# Rx_Universal_Schematic.net
KiCad netlist of a schematic drawn in Altium Designer
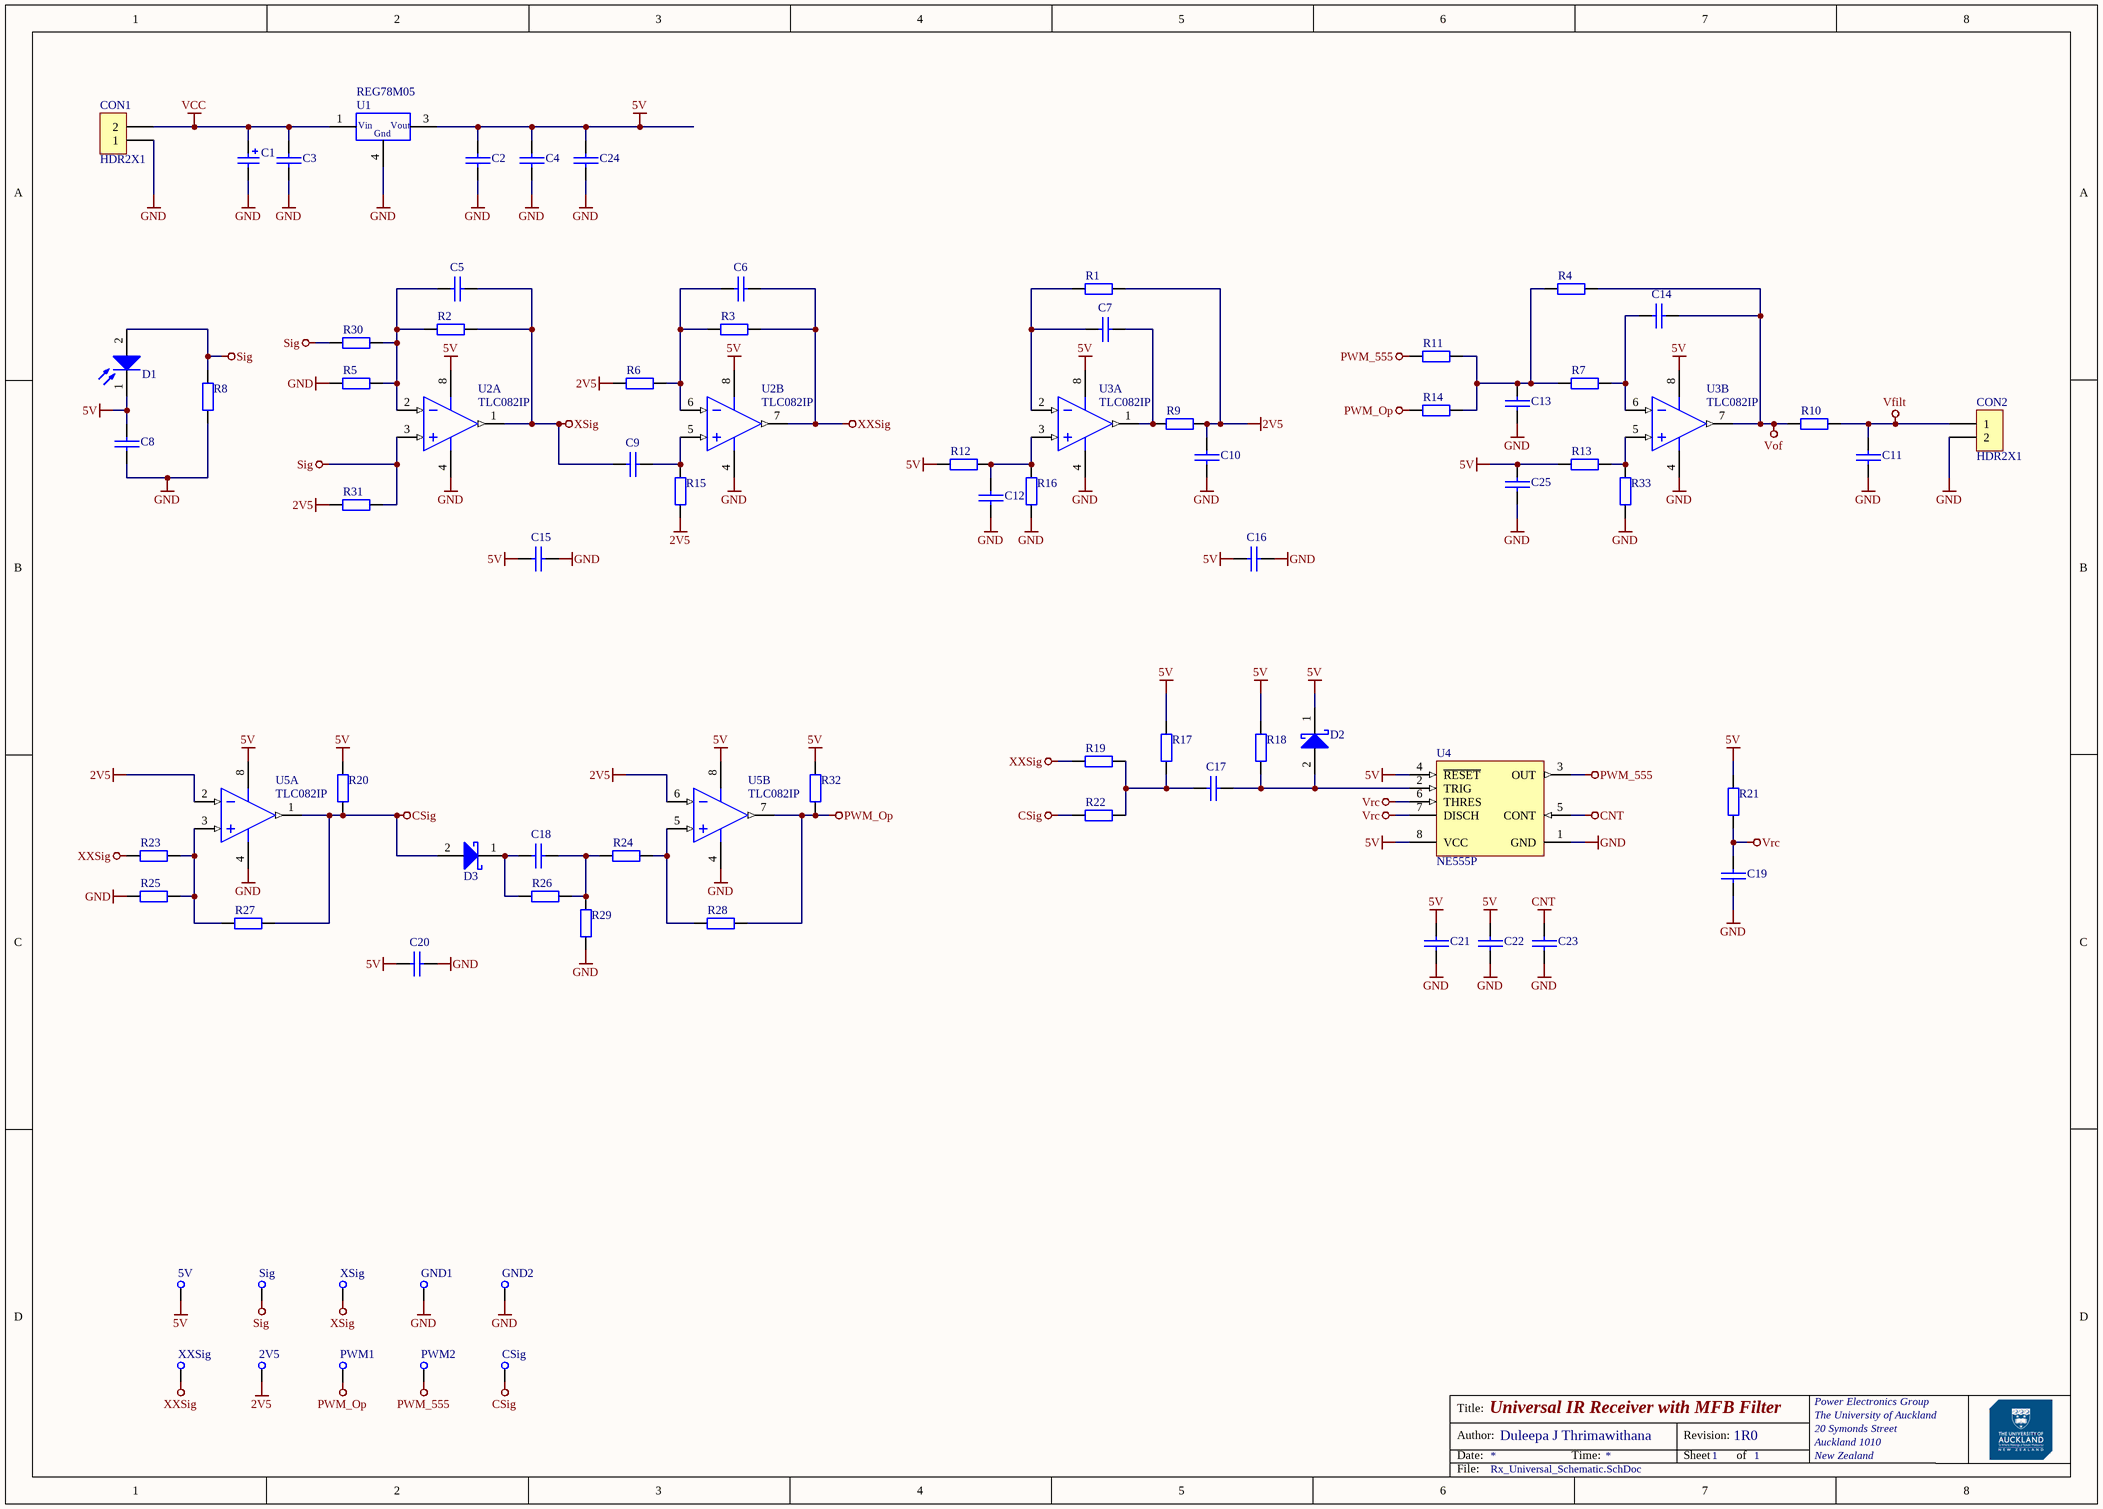
[diagram p0: Rx_Universal_Schematic.SchDoc]

(export (version "E")
  (design (tool "Eeschema 10.0.6"))
  (components
    (comp (ref "2V5")
      (value "TP TH")
      (footprint "TP_TH_2.5mm")
      (fields (field (name "SOURCE") "UoAPE_Connectors and Mechanical.SchLib"))
      (libsource (lib "ECSE@UoA") (part "TP TH"))
    )
    (comp (ref "5V")
      (value "TP TH")
      (footprint "TP_TH_2.5mm")
      (fields (field (name "SOURCE") "UoAPE_Connectors and Mechanical.SchLib"))
      (libsource (lib "ECSE@UoA") (part "TP TH"))
    )
    (comp (ref "C1") (value "ECAP") (footprint "CR05") (libsource (lib "ECSE@UoA") (part "ECAP")))
    (comp (ref "C2")
      (value "CCAP_TH_5P0")
      (footprint "CCAP_5P0")
      (description "TH ceramic cap with 5mm pitch")
      (libsource (lib "") (part "Symbol_3"))
    )
    (comp (ref "C3")
      (value "CCAP_TH_5P0")
      (footprint "CCAP_5P0")
      (description "TH ceramic cap with 5mm pitch")
      (libsource (lib "") (part "Symbol_3"))
    )
    (comp (ref "C4")
      (value "CCAP_TH_5P0")
      (footprint "CCAP_5P0")
      (description "TH ceramic cap with 5mm pitch")
      (libsource (lib "") (part "Symbol_3"))
    )
    (comp (ref "C5")
      (value "CCAP_TH_5P0")
      (footprint "CCAP_5P0")
      (description "TH ceramic cap with 5mm pitch")
      (libsource (lib "") (part "Symbol_3"))
    )
    (comp (ref "C6")
      (value "CCAP_TH_5P0")
      (footprint "CCAP_5P0")
      (description "TH ceramic cap with 5mm pitch")
      (libsource (lib "") (part "Symbol_3"))
    )
    (comp (ref "C7")
      (value "CCAP_TH_5P0")
      (footprint "CCAP_5P0")
      (description "TH ceramic cap with 5mm pitch")
      (libsource (lib "") (part "Symbol_3"))
    )
    (comp (ref "C8")
      (value "CCAP_TH_5P0")
      (footprint "CCAP_5P0")
      (description "TH ceramic cap with 5mm pitch")
      (libsource (lib "") (part "Symbol_3"))
    )
    (comp (ref "C9")
      (value "CCAP_TH_5P0")
      (footprint "CCAP_5P0")
      (description "TH ceramic cap with 5mm pitch")
      (libsource (lib "") (part "Symbol_3"))
    )
    (comp (ref "C10")
      (value "CCAP_TH_5P0")
      (footprint "CCAP_5P0")
      (description "TH ceramic cap with 5mm pitch")
      (libsource (lib "") (part "Symbol_3"))
    )
    (comp (ref "C11")
      (value "CCAP_TH_5P0")
      (footprint "CCAP_5P0")
      (description "TH ceramic cap with 5mm pitch")
      (libsource (lib "") (part "Symbol_3"))
    )
    (comp (ref "C12")
      (value "CCAP_TH_5P0")
      (footprint "CCAP_5P0")
      (description "TH ceramic cap with 5mm pitch")
      (libsource (lib "") (part "Symbol_3"))
    )
    (comp (ref "C13")
      (value "CCAP_TH_5P0")
      (footprint "CCAP_5P0")
      (description "TH ceramic cap with 5mm pitch")
      (libsource (lib "") (part "Symbol_3"))
    )
    (comp (ref "C14")
      (value "CCAP_TH_5P0")
      (footprint "CCAP_5P0")
      (description "TH ceramic cap with 5mm pitch")
      (libsource (lib "") (part "Symbol_3"))
    )
    (comp (ref "C15")
      (value "CCAP_TH_5P0")
      (footprint "CCAP_5P0")
      (description "TH ceramic cap with 5mm pitch")
      (libsource (lib "") (part "Symbol_3"))
    )
    (comp (ref "C16")
      (value "CCAP_TH_5P0")
      (footprint "CCAP_5P0")
      (description "TH ceramic cap with 5mm pitch")
      (libsource (lib "") (part "Symbol_3"))
    )
    (comp (ref "C17")
      (value "CCAP_TH_5P0")
      (footprint "CCAP_5P0")
      (description "TH ceramic cap with 5mm pitch")
      (libsource (lib "") (part "Symbol_3"))
    )
    (comp (ref "C18")
      (value "CCAP_TH_5P0")
      (footprint "CCAP_5P0")
      (description "TH ceramic cap with 5mm pitch")
      (libsource (lib "") (part "Symbol_3"))
    )
    (comp (ref "C19")
      (value "CCAP_TH_5P0")
      (footprint "CCAP_5P0")
      (description "TH ceramic cap with 5mm pitch")
      (libsource (lib "") (part "Symbol_3"))
    )
    (comp (ref "C20")
      (value "CCAP_TH_5P0")
      (footprint "CCAP_5P0")
      (description "TH ceramic cap with 5mm pitch")
      (libsource (lib "") (part "Symbol_3"))
    )
    (comp (ref "C21")
      (value "CCAP_TH_5P0")
      (footprint "CCAP_5P0")
      (description "TH ceramic cap with 5mm pitch")
      (libsource (lib "") (part "Symbol_3"))
    )
    (comp (ref "C22")
      (value "CCAP_TH_5P0")
      (footprint "CCAP_5P0")
      (description "TH ceramic cap with 5mm pitch")
      (libsource (lib "") (part "Symbol_3"))
    )
    (comp (ref "C23")
      (value "CCAP_TH_5P0")
      (footprint "CCAP_5P0")
      (description "TH ceramic cap with 5mm pitch")
      (libsource (lib "") (part "Symbol_3"))
    )
    (comp (ref "C24")
      (value "CCAP_TH_5P0")
      (footprint "CCAP_5P0")
      (description "TH ceramic cap with 5mm pitch")
      (libsource (lib "") (part "Symbol_3"))
    )
    (comp (ref "C25")
      (value "CCAP_TH_5P0")
      (footprint "CCAP_5P0")
      (description "TH ceramic cap with 5mm pitch")
      (libsource (lib "") (part "Symbol_3"))
    )
    (comp (ref "CON1")
      (value "HDR2X1")
      (footprint "HDR2X1_2P54")
      (description "Header 2X1")
      (libsource (lib "") (part "HDR2X1_1"))
    )
    (comp (ref "CON2")
      (value "HDR2X1")
      (footprint "HDR2X1_2P54")
      (description "Header 2X1")
      (libsource (lib "ECSE@UoA") (part "HDR2X1"))
    )
    (comp (ref "CSig")
      (value "TP TH")
      (footprint "TP_TH_2.5mm")
      (fields (field (name "SOURCE") "UoAPE_Connectors and Mechanical.SchLib"))
      (libsource (lib "ECSE@UoA") (part "TP TH"))
    )
    (comp (ref "D1")
      (value "PhotoD_TH")
      (footprint "TH_LED")
      (description "Photo diode")
      (libsource (lib "ECSE@UoA") (part "Copy of 8706943c75ba83719d021d2fdc84c58"))
    )
    (comp (ref "D2")
      (value "BAT85,113")
      (footprint "FP-SOD68-MFG")
      (description "Rectifier Diode, Schottky, 1 Phase, 1 Element, 0.2A, 30V V(RRM), Silicon, DO-34")
      (libsource (lib "ECSE@UoA") (part "1d6ec82d83fb6aee721767c19dac4b9"))
    )
    (comp (ref "D3")
      (value "BAT85,113")
      (footprint "FP-SOD68-MFG")
      (description "Rectifier Diode, Schottky, 1 Phase, 1 Element, 0.2A, 30V V(RRM), Silicon, DO-34")
      (libsource (lib "ECSE@UoA") (part "1d6ec82d83fb6aee721767c19dac4b9"))
    )
    (comp (ref "GND1")
      (value "TP TH")
      (footprint "TP_TH_2.5mm")
      (fields (field (name "SOURCE") "UoAPE_Connectors and Mechanical.SchLib"))
      (libsource (lib "ECSE@UoA") (part "TP TH"))
    )
    (comp (ref "GND2")
      (value "TP TH")
      (footprint "TP_TH_2.5mm")
      (fields (field (name "SOURCE") "UoAPE_Connectors and Mechanical.SchLib"))
      (libsource (lib "ECSE@UoA") (part "TP TH"))
    )
    (comp (ref "PWM1")
      (value "TP TH")
      (footprint "TP_TH_2.5mm")
      (fields (field (name "SOURCE") "UoAPE_Connectors and Mechanical.SchLib"))
      (libsource (lib "ECSE@UoA") (part "TP TH"))
    )
    (comp (ref "PWM2")
      (value "TP TH")
      (footprint "TP_TH_2.5mm")
      (fields (field (name "SOURCE") "UoAPE_Connectors and Mechanical.SchLib"))
      (libsource (lib "ECSE@UoA") (part "TP TH"))
    )
    (comp (ref "R1")
      (value "RESAX4")
      (footprint "RAX4")
      (description "Axial Resistor")
      (libsource (lib "ECSE@UoA") (part "Symbol"))
    )
    (comp (ref "R2")
      (value "RESAX4")
      (footprint "RAX4")
      (description "Axial Resistor")
      (libsource (lib "ECSE@UoA") (part "Symbol"))
    )
    (comp (ref "R3")
      (value "RESAX4")
      (footprint "RAX4")
      (description "Axial Resistor")
      (libsource (lib "ECSE@UoA") (part "Symbol"))
    )
    (comp (ref "R4")
      (value "RESAX4")
      (footprint "RAX4")
      (description "Axial Resistor")
      (libsource (lib "ECSE@UoA") (part "Symbol"))
    )
    (comp (ref "R5")
      (value "RESAX4")
      (footprint "RAX4")
      (description "Axial Resistor")
      (libsource (lib "ECSE@UoA") (part "Symbol"))
    )
    (comp (ref "R6")
      (value "RESAX4")
      (footprint "RAX4")
      (description "Axial Resistor")
      (libsource (lib "ECSE@UoA") (part "Symbol"))
    )
    (comp (ref "R7")
      (value "RESAX4")
      (footprint "RAX4")
      (description "Axial Resistor")
      (libsource (lib "ECSE@UoA") (part "Symbol"))
    )
    (comp (ref "R8")
      (value "RESAX4")
      (footprint "RAX4")
      (description "Axial Resistor")
      (libsource (lib "") (part "Symbol_2"))
    )
    (comp (ref "R9")
      (value "RESAX4")
      (footprint "RAX4")
      (description "Axial Resistor")
      (libsource (lib "ECSE@UoA") (part "Symbol"))
    )
    (comp (ref "R10")
      (value "RESAX4")
      (footprint "RAX4")
      (description "Axial Resistor")
      (libsource (lib "ECSE@UoA") (part "Symbol"))
    )
    (comp (ref "R11")
      (value "RESAX4")
      (footprint "RAX4")
      (description "Axial Resistor")
      (libsource (lib "ECSE@UoA") (part "Symbol"))
    )
    (comp (ref "R12")
      (value "RESAX4")
      (footprint "RAX4")
      (description "Axial Resistor")
      (libsource (lib "ECSE@UoA") (part "Symbol"))
    )
    (comp (ref "R13")
      (value "RESAX4")
      (footprint "RAX4")
      (description "Axial Resistor")
      (libsource (lib "ECSE@UoA") (part "Symbol"))
    )
    (comp (ref "R14")
      (value "RESAX4")
      (footprint "RAX4")
      (description "Axial Resistor")
      (libsource (lib "ECSE@UoA") (part "Symbol"))
    )
    (comp (ref "R15")
      (value "RESAX4")
      (footprint "RAX4")
      (description "Axial Resistor")
      (libsource (lib "") (part "Symbol_2"))
    )
    (comp (ref "R16")
      (value "RESAX4")
      (footprint "RAX4")
      (description "Axial Resistor")
      (libsource (lib "") (part "Symbol_2"))
    )
    (comp (ref "R17")
      (value "RESAX4")
      (footprint "RAX4")
      (description "Axial Resistor")
      (libsource (lib "") (part "Symbol_2"))
    )
    (comp (ref "R18")
      (value "RESAX4")
      (footprint "RAX4")
      (description "Axial Resistor")
      (libsource (lib "") (part "Symbol_2"))
    )
    (comp (ref "R19")
      (value "RESAX4")
      (footprint "RAX4")
      (description "Axial Resistor")
      (libsource (lib "ECSE@UoA") (part "Symbol"))
    )
    (comp (ref "R20")
      (value "RESAX4")
      (footprint "RAX4")
      (description "Axial Resistor")
      (libsource (lib "") (part "Symbol_1"))
    )
    (comp (ref "R21")
      (value "RESAX4")
      (footprint "RAX4")
      (description "Axial Resistor")
      (libsource (lib "") (part "Symbol_2"))
    )
    (comp (ref "R22")
      (value "RESAX4")
      (footprint "RAX4")
      (description "Axial Resistor")
      (libsource (lib "ECSE@UoA") (part "Symbol"))
    )
    (comp (ref "R23")
      (value "RESAX4")
      (footprint "RAX4")
      (description "Axial Resistor")
      (libsource (lib "ECSE@UoA") (part "Symbol"))
    )
    (comp (ref "R24")
      (value "RESAX4")
      (footprint "RAX4")
      (description "Axial Resistor")
      (libsource (lib "ECSE@UoA") (part "Symbol"))
    )
    (comp (ref "R25")
      (value "RESAX4")
      (footprint "RAX4")
      (description "Axial Resistor")
      (libsource (lib "ECSE@UoA") (part "Symbol"))
    )
    (comp (ref "R26")
      (value "RESAX4")
      (footprint "RAX4")
      (description "Axial Resistor")
      (libsource (lib "ECSE@UoA") (part "Symbol"))
    )
    (comp (ref "R27")
      (value "RESAX4")
      (footprint "RAX4")
      (description "Axial Resistor")
      (libsource (lib "ECSE@UoA") (part "Symbol"))
    )
    (comp (ref "R28")
      (value "RESAX4")
      (footprint "RAX4")
      (description "Axial Resistor")
      (libsource (lib "ECSE@UoA") (part "Symbol"))
    )
    (comp (ref "R29")
      (value "RESAX4")
      (footprint "RAX4")
      (description "Axial Resistor")
      (libsource (lib "") (part "Symbol_1"))
    )
    (comp (ref "R30")
      (value "RESAX4")
      (footprint "RAX4")
      (description "Axial Resistor")
      (libsource (lib "ECSE@UoA") (part "Symbol"))
    )
    (comp (ref "R31")
      (value "RESAX4")
      (footprint "RAX4")
      (description "Axial Resistor")
      (libsource (lib "ECSE@UoA") (part "Symbol"))
    )
    (comp (ref "R32")
      (value "RESAX4")
      (footprint "RAX4")
      (description "Axial Resistor")
      (libsource (lib "") (part "Symbol_1"))
    )
    (comp (ref "R33")
      (value "RESAX4")
      (footprint "RAX4")
      (description "Axial Resistor")
      (libsource (lib "") (part "Symbol_1"))
    )
    (comp (ref "Sig")
      (value "TP TH")
      (footprint "TP_TH_2.5mm")
      (fields (field (name "SOURCE") "UoAPE_Connectors and Mechanical.SchLib"))
      (libsource (lib "ECSE@UoA") (part "TP TH"))
    )
    (comp (ref "U1")
      (value "REG78M05")
      (footprint "TO220_Reg")
      (description "78M Series Linear Regulators")
      (libsource (lib "ECSE@UoA") (part "REG78MXX"))
    )
    (comp (ref "U2")
      (value "TLC082IP")
      (footprint "P0008A")
      (description "Operational Amplifier, 2 Func, 3000uV Offset-Max, BIMOS, PDIP8")
      (fields (field (name "POWER") "100mW"))
      (libsource (lib "ECSE@UoA") (part "TI-TLV_TLC-8"))
    )
    (comp (ref "U3")
      (value "TLC082IP")
      (footprint "P0008A")
      (description "Operational Amplifier, 2 Func, 3000uV Offset-Max, BIMOS, PDIP8")
      (fields (field (name "POWER") "100mW"))
      (libsource (lib "ECSE@UoA") (part "TI-TLV_TLC-8"))
    )
    (comp (ref "U4")
      (value "NE555P")
      (footprint "P0008A")
      (description "1 Func, BIPolar, PDIP8")
      (libsource (lib "ECSE@UoA") (part "TI-NE555-P8"))
    )
    (comp (ref "U5")
      (value "TLC082IP")
      (footprint "P0008A")
      (description "Operational Amplifier, 2 Func, 3000uV Offset-Max, BIMOS, PDIP8")
      (fields (field (name "POWER") "100mW"))
      (libsource (lib "ECSE@UoA") (part "TI-TLV_TLC-8"))
    )
    (comp (ref "XSig")
      (value "TP TH")
      (footprint "TP_TH_2.5mm")
      (fields (field (name "SOURCE") "UoAPE_Connectors and Mechanical.SchLib"))
      (libsource (lib "ECSE@UoA") (part "TP TH"))
    )
    (comp (ref "XXSig")
      (value "TP TH")
      (footprint "TP_TH_2.5mm")
      (fields (field (name "SOURCE") "UoAPE_Connectors and Mechanical.SchLib"))
      (libsource (lib "ECSE@UoA") (part "TP TH"))
    )
  )
  (nets
    (net (code "1") (name "2V5") (class "Default")
      (node (ref "2V5") (pin "1") (pinfunction "1_1") (pintype "passive"))
      (node (ref "C10") (pin "1") (pinfunction "1_1") (pintype "passive"))
      (node (ref "R1") (pin "1") (pinfunction "1_1") (pintype "passive"))
      (node (ref "R15") (pin "1") (pinfunction "1_1") (pintype "passive"))
      (node (ref "R31") (pin "2") (pinfunction "2_2") (pintype "passive"))
      (node (ref "R6") (pin "2") (pinfunction "2_2") (pintype "passive"))
      (node (ref "R9") (pin "1") (pinfunction "1_1") (pintype "passive"))
      (node (ref "U5") (pin "2") (pinfunction "IN1-_2") (pintype "input"))
      (node (ref "U5") (pin "6") (pinfunction "IN2-_6") (pintype "input"))
    )
    (net (code "2") (name "5V") (class "Default")
      (node (ref "5V") (pin "1") (pinfunction "1_1") (pintype "passive"))
      (node (ref "C15") (pin "2") (pinfunction "2_2") (pintype "passive"))
      (node (ref "C16") (pin "2") (pinfunction "2_2") (pintype "passive"))
      (node (ref "C2") (pin "2") (pinfunction "2_2") (pintype "passive"))
      (node (ref "C20") (pin "2") (pinfunction "2_2") (pintype "passive"))
      (node (ref "C21") (pin "2") (pinfunction "2_2") (pintype "passive"))
      (node (ref "C22") (pin "2") (pinfunction "2_2") (pintype "passive"))
      (node (ref "C24") (pin "2") (pinfunction "2_2") (pintype "passive"))
      (node (ref "C25") (pin "2") (pinfunction "2_2") (pintype "passive"))
      (node (ref "C4") (pin "2") (pinfunction "2_2") (pintype "passive"))
      (node (ref "C8") (pin "2") (pinfunction "2_2") (pintype "passive"))
      (node (ref "D1") (pin "1") (pinfunction "C_1") (pintype "passive"))
      (node (ref "D2") (pin "1") (pinfunction "C_1") (pintype "passive"))
      (node (ref "R12") (pin "2") (pinfunction "2_2") (pintype "passive"))
      (node (ref "R13") (pin "2") (pinfunction "2_2") (pintype "passive"))
      (node (ref "R17") (pin "2") (pinfunction "2_2") (pintype "passive"))
      (node (ref "R18") (pin "2") (pinfunction "2_2") (pintype "passive"))
      (node (ref "R20") (pin "1") (pinfunction "1_1") (pintype "passive"))
      (node (ref "R21") (pin "2") (pinfunction "2_2") (pintype "passive"))
      (node (ref "R32") (pin "1") (pinfunction "1_1") (pintype "passive"))
      (node (ref "U1") (pin "3") (pinfunction "Vout_3") (pintype "passive"))
      (node (ref "U2") (pin "8") (pinfunction "VDD_8") (pintype "power_in"))
      (node (ref "U3") (pin "8") (pinfunction "VDD_8") (pintype "power_in"))
      (node (ref "U4") (pin "4") (pinfunction "~{RESET}_4") (pintype "input"))
      (node (ref "U4") (pin "8") (pinfunction "VCC_8") (pintype "power_in"))
      (node (ref "U5") (pin "8") (pinfunction "VDD_8") (pintype "power_in"))
    )
    (net (code "3") (name "CNT") (class "Default")
      (node (ref "C23") (pin "2") (pinfunction "2_2") (pintype "passive"))
      (node (ref "U4") (pin "5") (pinfunction "CONT_5") (pintype "input"))
    )
    (net (code "4") (name "CSig") (class "Default")
      (node (ref "CSig") (pin "1") (pinfunction "1_1") (pintype "passive"))
      (node (ref "D3") (pin "2") (pinfunction "A_2") (pintype "passive"))
      (node (ref "R20") (pin "2") (pinfunction "2_2") (pintype "passive"))
      (node (ref "R22") (pin "2") (pinfunction "2_2") (pintype "passive"))
      (node (ref "R27") (pin "1") (pinfunction "1_1") (pintype "passive"))
      (node (ref "U5") (pin "1") (pinfunction "OUT1_1") (pintype "output"))
    )
    (net (code "5") (name "GND") (class "Default")
      (node (ref "C1") (pin "2") (pinfunction "2_2") (pintype "passive"))
      (node (ref "C10") (pin "2") (pinfunction "2_2") (pintype "passive"))
      (node (ref "C11") (pin "1") (pinfunction "1_1") (pintype "passive"))
      (node (ref "C12") (pin "2") (pinfunction "2_2") (pintype "passive"))
      (node (ref "C13") (pin "1") (pinfunction "1_1") (pintype "passive"))
      (node (ref "C15") (pin "1") (pinfunction "1_1") (pintype "passive"))
      (node (ref "C16") (pin "1") (pinfunction "1_1") (pintype "passive"))
      (node (ref "C19") (pin "1") (pinfunction "1_1") (pintype "passive"))
      (node (ref "C2") (pin "1") (pinfunction "1_1") (pintype "passive"))
      (node (ref "C20") (pin "1") (pinfunction "1_1") (pintype "passive"))
      (node (ref "C21") (pin "1") (pinfunction "1_1") (pintype "passive"))
      (node (ref "C22") (pin "1") (pinfunction "1_1") (pintype "passive"))
      (node (ref "C23") (pin "1") (pinfunction "1_1") (pintype "passive"))
      (node (ref "C24") (pin "1") (pinfunction "1_1") (pintype "passive"))
      (node (ref "C25") (pin "1") (pinfunction "1_1") (pintype "passive"))
      (node (ref "C3") (pin "1") (pinfunction "1_1") (pintype "passive"))
      (node (ref "C4") (pin "1") (pinfunction "1_1") (pintype "passive"))
      (node (ref "C8") (pin "1") (pinfunction "1_1") (pintype "passive"))
      (node (ref "CON1") (pin "1") (pinfunction "1_1") (pintype "passive"))
      (node (ref "CON2") (pin "2") (pinfunction "2_2") (pintype "passive"))
      (node (ref "GND1") (pin "1") (pinfunction "1_1") (pintype "passive"))
      (node (ref "GND2") (pin "1") (pinfunction "1_1") (pintype "passive"))
      (node (ref "R16") (pin "1") (pinfunction "1_1") (pintype "passive"))
      (node (ref "R25") (pin "2") (pinfunction "2_2") (pintype "passive"))
      (node (ref "R29") (pin "2") (pinfunction "2_2") (pintype "passive"))
      (node (ref "R33") (pin "2") (pinfunction "2_2") (pintype "passive"))
      (node (ref "R5") (pin "2") (pinfunction "2_2") (pintype "passive"))
      (node (ref "R8") (pin "1") (pinfunction "1_1") (pintype "passive"))
      (node (ref "U1") (pin "4") (pinfunction "Gnd_4") (pintype "passive"))
      (node (ref "U2") (pin "4") (pinfunction "GND_4") (pintype "power_in"))
      (node (ref "U3") (pin "4") (pinfunction "GND_4") (pintype "power_in"))
      (node (ref "U4") (pin "1") (pinfunction "GND_1") (pintype "power_in"))
      (node (ref "U5") (pin "4") (pinfunction "GND_4") (pintype "power_in"))
    )
    (net (code "6") (name "Net-(C13-Pad2)") (class "Default")
      (node (ref "C13") (pin "2") (pinfunction "2_2") (pintype "passive"))
      (node (ref "R11") (pin "1") (pinfunction "1_1") (pintype "passive"))
      (node (ref "R14") (pin "1") (pinfunction "1_1") (pintype "passive"))
      (node (ref "R4") (pin "2") (pinfunction "2_2") (pintype "passive"))
      (node (ref "R7") (pin "2") (pinfunction "2_2") (pintype "passive"))
    )
    (net (code "7") (name "Net-(C17-Pad2)") (class "Default")
      (node (ref "C17") (pin "2") (pinfunction "2_2") (pintype "passive"))
      (node (ref "R17") (pin "1") (pinfunction "1_1") (pintype "passive"))
      (node (ref "R19") (pin "1") (pinfunction "1_1") (pintype "passive"))
      (node (ref "R22") (pin "1") (pinfunction "1_1") (pintype "passive"))
    )
    (net (code "8") (name "Net-(C18-Pad1)") (class "Default")
      (node (ref "C18") (pin "1") (pinfunction "1_1") (pintype "passive"))
      (node (ref "R24") (pin "2") (pinfunction "2_2") (pintype "passive"))
      (node (ref "R26") (pin "1") (pinfunction "1_1") (pintype "passive"))
      (node (ref "R29") (pin "1") (pinfunction "1_1") (pintype "passive"))
    )
    (net (code "9") (name "Net-(D2-A)") (class "Default")
      (node (ref "C17") (pin "1") (pinfunction "1_1") (pintype "passive"))
      (node (ref "D2") (pin "2") (pinfunction "A_2") (pintype "passive"))
      (node (ref "R18") (pin "1") (pinfunction "1_1") (pintype "passive"))
      (node (ref "U4") (pin "2") (pinfunction "TRIG_2") (pintype "input"))
    )
    (net (code "10") (name "Net-(D3-C)") (class "Default")
      (node (ref "C18") (pin "2") (pinfunction "2_2") (pintype "passive"))
      (node (ref "D3") (pin "1") (pinfunction "C_1") (pintype "passive"))
      (node (ref "R26") (pin "2") (pinfunction "2_2") (pintype "passive"))
    )
    (net (code "11") (name "Net-(U2A-IN1-)") (class "Default")
      (node (ref "C5") (pin "2") (pinfunction "2_2") (pintype "passive"))
      (node (ref "R2") (pin "2") (pinfunction "2_2") (pintype "passive"))
      (node (ref "R30") (pin "1") (pinfunction "1_1") (pintype "passive"))
      (node (ref "R5") (pin "1") (pinfunction "1_1") (pintype "passive"))
      (node (ref "U2") (pin "2") (pinfunction "IN1-_2") (pintype "input"))
    )
    (net (code "12") (name "Net-(U2B-IN2+)") (class "Default")
      (node (ref "C9") (pin "1") (pinfunction "1_1") (pintype "passive"))
      (node (ref "R15") (pin "2") (pinfunction "2_2") (pintype "passive"))
      (node (ref "U2") (pin "5") (pinfunction "IN2+_5") (pintype "input"))
    )
    (net (code "13") (name "Net-(U2B-IN2-)") (class "Default")
      (node (ref "C6") (pin "2") (pinfunction "2_2") (pintype "passive"))
      (node (ref "R3") (pin "2") (pinfunction "2_2") (pintype "passive"))
      (node (ref "R6") (pin "1") (pinfunction "1_1") (pintype "passive"))
      (node (ref "U2") (pin "6") (pinfunction "IN2-_6") (pintype "input"))
    )
    (net (code "14") (name "Net-(U3A-IN1+)") (class "Default")
      (node (ref "C12") (pin "1") (pinfunction "1_1") (pintype "passive"))
      (node (ref "R12") (pin "1") (pinfunction "1_1") (pintype "passive"))
      (node (ref "R16") (pin "2") (pinfunction "2_2") (pintype "passive"))
      (node (ref "U3") (pin "3") (pinfunction "IN1+_3") (pintype "input"))
    )
    (net (code "15") (name "Net-(U3A-IN1-)") (class "Default")
      (node (ref "C7") (pin "2") (pinfunction "2_2") (pintype "passive"))
      (node (ref "R1") (pin "2") (pinfunction "2_2") (pintype "passive"))
      (node (ref "U3") (pin "2") (pinfunction "IN1-_2") (pintype "input"))
    )
    (net (code "16") (name "Net-(U3A-OUT1)") (class "Default")
      (node (ref "C7") (pin "1") (pinfunction "1_1") (pintype "passive"))
      (node (ref "R9") (pin "2") (pinfunction "2_2") (pintype "passive"))
      (node (ref "U3") (pin "1") (pinfunction "OUT1_1") (pintype "output"))
    )
    (net (code "17") (name "Net-(U3B-IN2+)") (class "Default")
      (node (ref "R13") (pin "1") (pinfunction "1_1") (pintype "passive"))
      (node (ref "R33") (pin "1") (pinfunction "1_1") (pintype "passive"))
      (node (ref "U3") (pin "5") (pinfunction "IN2+_5") (pintype "input"))
    )
    (net (code "18") (name "Net-(U3B-IN2-)") (class "Default")
      (node (ref "C14") (pin "1") (pinfunction "1_1") (pintype "passive"))
      (node (ref "R7") (pin "1") (pinfunction "1_1") (pintype "passive"))
      (node (ref "U3") (pin "6") (pinfunction "IN2-_6") (pintype "input"))
    )
    (net (code "19") (name "Net-(U5A-IN1+)") (class "Default")
      (node (ref "R23") (pin "1") (pinfunction "1_1") (pintype "passive"))
      (node (ref "R25") (pin "1") (pinfunction "1_1") (pintype "passive"))
      (node (ref "R27") (pin "2") (pinfunction "2_2") (pintype "passive"))
      (node (ref "U5") (pin "3") (pinfunction "IN1+_3") (pintype "input"))
    )
    (net (code "20") (name "Net-(U5B-IN2+)") (class "Default")
      (node (ref "R24") (pin "1") (pinfunction "1_1") (pintype "passive"))
      (node (ref "R28") (pin "2") (pinfunction "2_2") (pintype "passive"))
      (node (ref "U5") (pin "5") (pinfunction "IN2+_5") (pintype "input"))
    )
    (net (code "21") (name "PWM_555") (class "Default")
      (node (ref "PWM2") (pin "1") (pinfunction "1_1") (pintype "passive"))
      (node (ref "R11") (pin "2") (pinfunction "2_2") (pintype "passive"))
      (node (ref "U4") (pin "3") (pinfunction "OUT_3") (pintype "output"))
    )
    (net (code "22") (name "PWM_Op") (class "Default")
      (node (ref "PWM1") (pin "1") (pinfunction "1_1") (pintype "passive"))
      (node (ref "R14") (pin "2") (pinfunction "2_2") (pintype "passive"))
      (node (ref "R28") (pin "1") (pinfunction "1_1") (pintype "passive"))
      (node (ref "R32") (pin "2") (pinfunction "2_2") (pintype "passive"))
      (node (ref "U5") (pin "7") (pinfunction "OUT2_7") (pintype "output"))
    )
    (net (code "23") (name "Sig") (class "Default")
      (node (ref "D1") (pin "2") (pinfunction "A_2") (pintype "passive"))
      (node (ref "R30") (pin "2") (pinfunction "2_2") (pintype "passive"))
      (node (ref "R31") (pin "1") (pinfunction "1_1") (pintype "passive"))
      (node (ref "R8") (pin "2") (pinfunction "2_2") (pintype "passive"))
      (node (ref "Sig") (pin "1") (pinfunction "1_1") (pintype "passive"))
      (node (ref "U2") (pin "3") (pinfunction "IN1+_3") (pintype "input"))
    )
    (net (code "24") (name "VCC") (class "Default")
      (node (ref "C1") (pin "1") (pinfunction "1_1") (pintype "passive"))
      (node (ref "C3") (pin "2") (pinfunction "2_2") (pintype "passive"))
      (node (ref "CON1") (pin "2") (pinfunction "2_2") (pintype "passive"))
      (node (ref "U1") (pin "1") (pinfunction "Vin_1") (pintype "passive"))
    )
    (net (code "25") (name "Vfilt") (class "Default")
      (node (ref "C11") (pin "2") (pinfunction "2_2") (pintype "passive"))
      (node (ref "CON2") (pin "1") (pinfunction "1_1") (pintype "passive"))
      (node (ref "R10") (pin "1") (pinfunction "1_1") (pintype "passive"))
    )
    (net (code "26") (name "Vof") (class "Default")
      (node (ref "C14") (pin "2") (pinfunction "2_2") (pintype "passive"))
      (node (ref "R10") (pin "2") (pinfunction "2_2") (pintype "passive"))
      (node (ref "R4") (pin "1") (pinfunction "1_1") (pintype "passive"))
      (node (ref "U3") (pin "7") (pinfunction "OUT2_7") (pintype "output"))
    )
    (net (code "27") (name "Vrc") (class "Default")
      (node (ref "C19") (pin "2") (pinfunction "2_2") (pintype "passive"))
      (node (ref "R21") (pin "1") (pinfunction "1_1") (pintype "passive"))
      (node (ref "U4") (pin "6") (pinfunction "THRES_6") (pintype "input"))
      (node (ref "U4") (pin "7") (pinfunction "DISCH_7") (pintype "open_collector"))
    )
    (net (code "28") (name "XSig") (class "Default")
      (node (ref "C5") (pin "1") (pinfunction "1_1") (pintype "passive"))
      (node (ref "C9") (pin "2") (pinfunction "2_2") (pintype "passive"))
      (node (ref "R2") (pin "1") (pinfunction "1_1") (pintype "passive"))
      (node (ref "U2") (pin "1") (pinfunction "OUT1_1") (pintype "output"))
      (node (ref "XSig") (pin "1") (pinfunction "1_1") (pintype "passive"))
    )
    (net (code "29") (name "XXSig") (class "Default")
      (node (ref "C6") (pin "1") (pinfunction "1_1") (pintype "passive"))
      (node (ref "R19") (pin "2") (pinfunction "2_2") (pintype "passive"))
      (node (ref "R23") (pin "2") (pinfunction "2_2") (pintype "passive"))
      (node (ref "R3") (pin "1") (pinfunction "1_1") (pintype "passive"))
      (node (ref "U2") (pin "7") (pinfunction "OUT2_7") (pintype "output"))
      (node (ref "XXSig") (pin "1") (pinfunction "1_1") (pintype "passive"))
    )
  )
)
